# Schema_serre.net
KiCad netlist of a schematic drawn in EAGLE
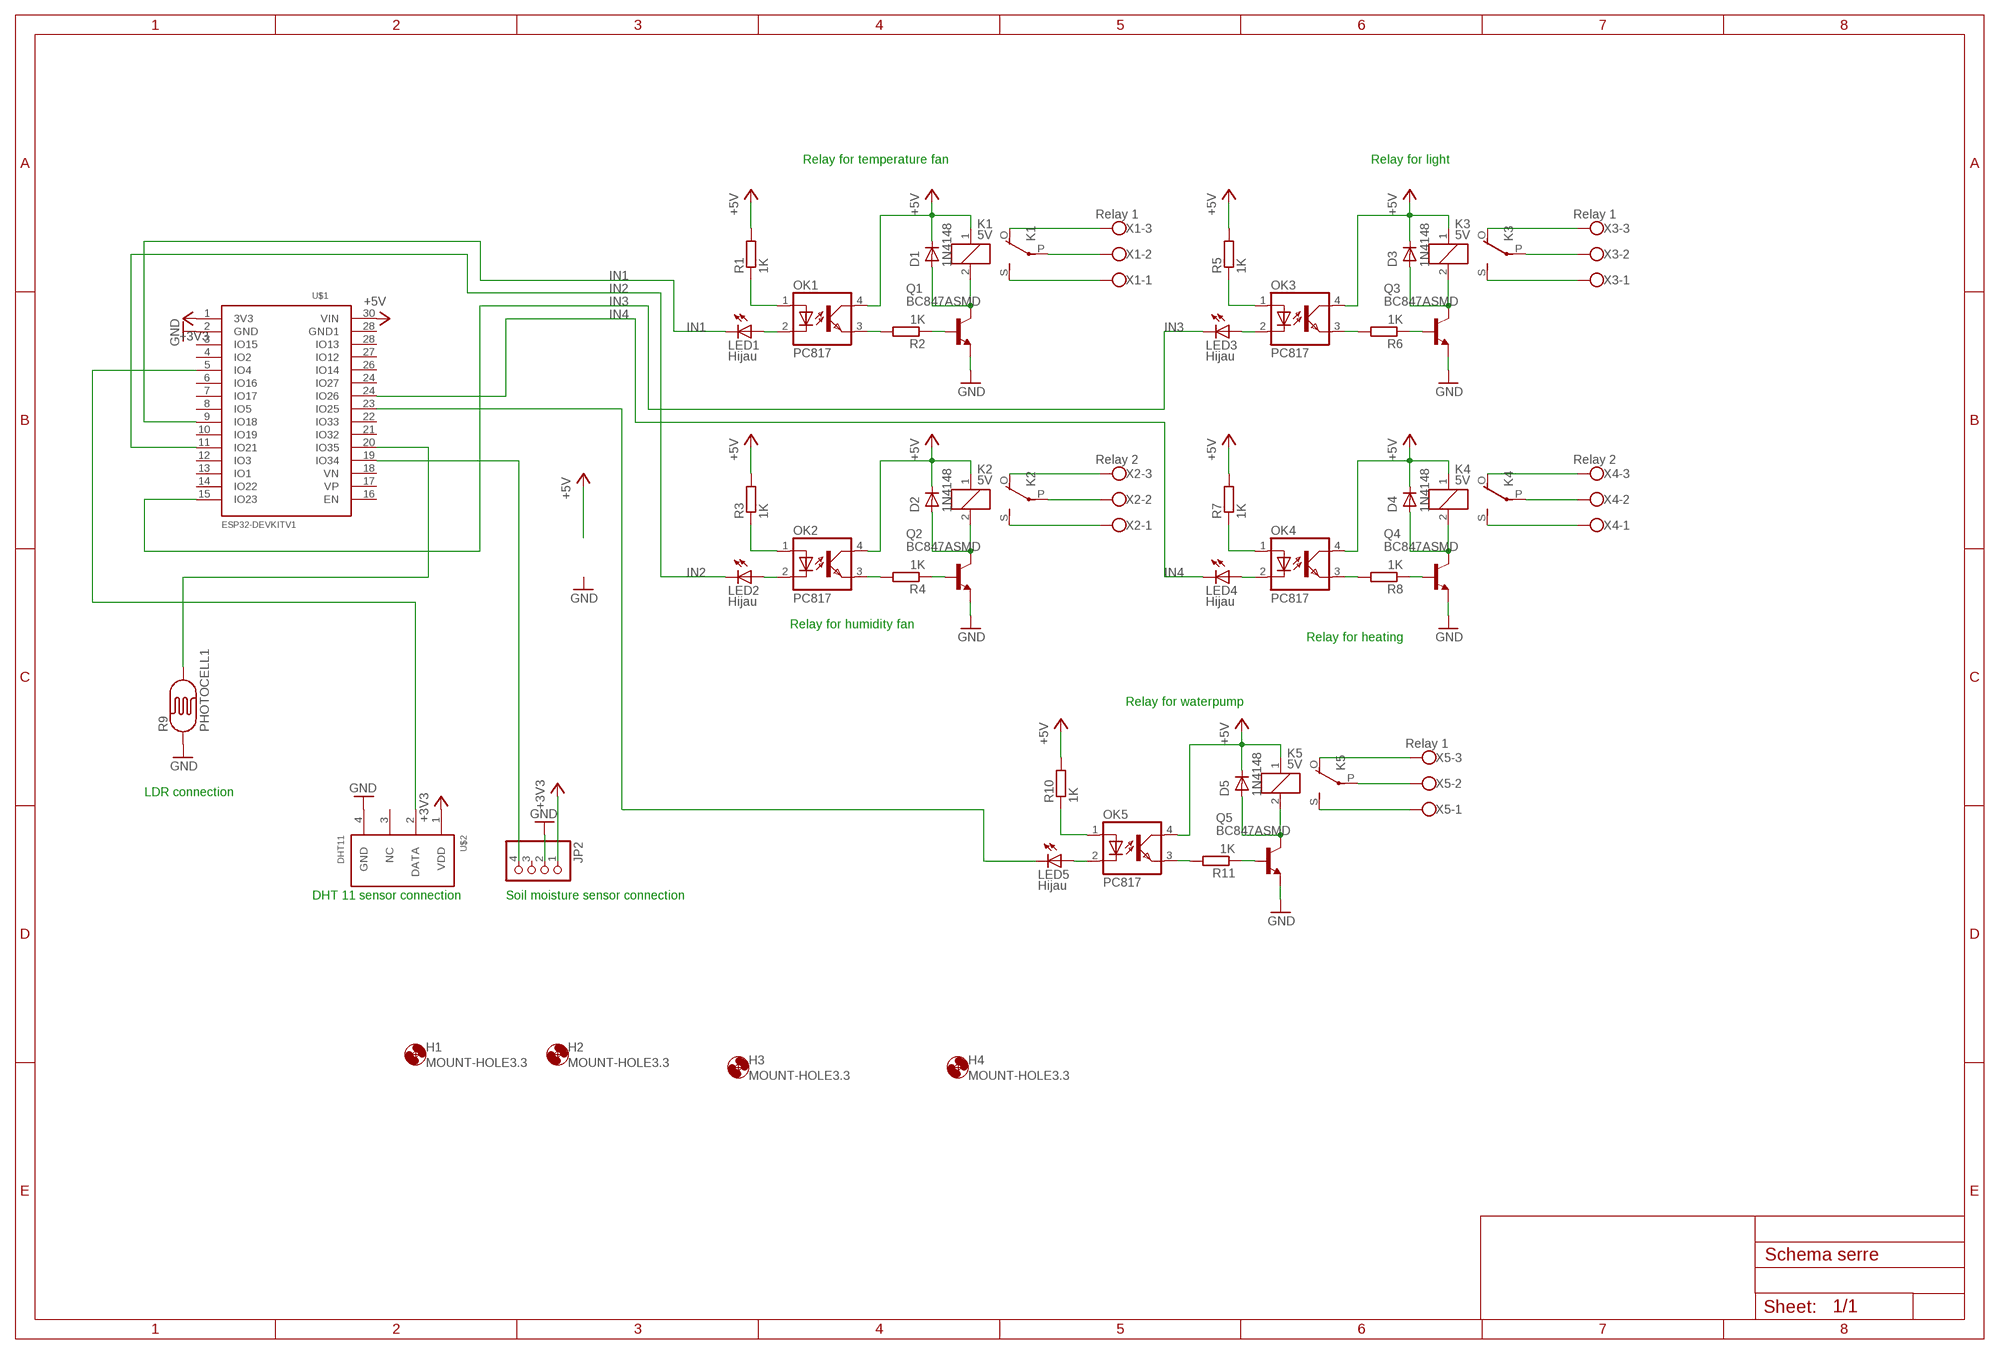
[diagram p0: schematic, sheet 1]

(export (version "E")
  (design (tool "Eeschema 10.0.6"))
  (components
    (comp (ref "D1")
      (value "1N4148")
      (footprint "eagle-import:SMA-DO214AC")
      (libsource (lib "eagle-import") (part "GF1"))
    )
    (comp (ref "D2")
      (value "1N4148")
      (footprint "eagle-import:SMA-DO214AC")
      (libsource (lib "eagle-import") (part "GF1"))
    )
    (comp (ref "D3")
      (value "1N4148")
      (footprint "eagle-import:SMA-DO214AC")
      (libsource (lib "eagle-import") (part "GF1"))
    )
    (comp (ref "D4")
      (value "1N4148")
      (footprint "eagle-import:SMA-DO214AC")
      (libsource (lib "eagle-import") (part "GF1"))
    )
    (comp (ref "D5")
      (value "1N4148")
      (footprint "eagle-import:SMA-DO214AC")
      (libsource (lib "eagle-import") (part "GF1"))
    )
    (comp (ref "H1")
      (value "MOUNT-HOLE3.3")
      (footprint "eagle-import:3,3")
      (libsource (lib "eagle-import") (part "MOUNT-HOLE3.3"))
    )
    (comp (ref "H2")
      (value "MOUNT-HOLE3.3")
      (footprint "eagle-import:3,3")
      (libsource (lib "eagle-import") (part "MOUNT-HOLE3.3"))
    )
    (comp (ref "H3")
      (value "MOUNT-HOLE3.3")
      (footprint "eagle-import:3,3")
      (libsource (lib "eagle-import") (part "MOUNT-HOLE3.3"))
    )
    (comp (ref "H4")
      (value "MOUNT-HOLE3.3")
      (footprint "eagle-import:3,3")
      (libsource (lib "eagle-import") (part "MOUNT-HOLE3.3"))
    )
    (comp (ref "JP2")
      (value "PINHD-1X4")
      (footprint "eagle-import:1X04")
      (libsource (lib "eagle-import") (part "PINHD-1X4"))
    )
    (comp (ref "K1")
      (value "5V")
      (footprint "eagle-import:ZF112")
      (libsource (lib "eagle-import") (part "ZF112"))
    )
    (comp (ref "K2")
      (value "5V")
      (footprint "eagle-import:ZF112")
      (libsource (lib "eagle-import") (part "ZF112"))
    )
    (comp (ref "K3")
      (value "5V")
      (footprint "eagle-import:ZF112")
      (libsource (lib "eagle-import") (part "ZF112"))
    )
    (comp (ref "K4")
      (value "5V")
      (footprint "eagle-import:ZF112")
      (libsource (lib "eagle-import") (part "ZF112"))
    )
    (comp (ref "K5")
      (value "5V")
      (footprint "eagle-import:ZF112")
      (libsource (lib "eagle-import") (part "ZF112"))
    )
    (comp (ref "LED1")
      (value "Hijau")
      (footprint "eagle-import:LED3MM")
      (libsource (lib "eagle-import") (part "LED3MM"))
    )
    (comp (ref "LED2")
      (value "Hijau")
      (footprint "eagle-import:LED3MM")
      (libsource (lib "eagle-import") (part "LED3MM"))
    )
    (comp (ref "LED3")
      (value "Hijau")
      (footprint "eagle-import:LED3MM")
      (libsource (lib "eagle-import") (part "LED3MM"))
    )
    (comp (ref "LED4")
      (value "Hijau")
      (footprint "eagle-import:LED3MM")
      (libsource (lib "eagle-import") (part "LED3MM"))
    )
    (comp (ref "LED5")
      (value "Hijau")
      (footprint "eagle-import:LED3MM")
      (libsource (lib "eagle-import") (part "LED3MM"))
    )
    (comp (ref "OK1")
      (value "PC817")
      (footprint "eagle-import:DIL04")
      (fields (field (name "MPN") "PC817X4J000F"))
      (libsource (lib "eagle-import") (part "PC817"))
    )
    (comp (ref "OK2")
      (value "PC817")
      (footprint "eagle-import:DIL04")
      (fields (field (name "MPN") "PC817X4J000F"))
      (libsource (lib "eagle-import") (part "PC817"))
    )
    (comp (ref "OK3")
      (value "PC817")
      (footprint "eagle-import:DIL04")
      (fields (field (name "MPN") "PC817X4J000F"))
      (libsource (lib "eagle-import") (part "PC817"))
    )
    (comp (ref "OK4")
      (value "PC817")
      (footprint "eagle-import:DIL04")
      (fields (field (name "MPN") "PC817X4J000F"))
      (libsource (lib "eagle-import") (part "PC817"))
    )
    (comp (ref "OK5")
      (value "PC817")
      (footprint "eagle-import:DIL04")
      (fields (field (name "MPN") "PC817X4J000F"))
      (libsource (lib "eagle-import") (part "PC817"))
    )
    (comp (ref "Q1")
      (value "BC847ASMD")
      (footprint "eagle-import:SOT23")
      (libsource (lib "eagle-import") (part "BC847SMDA"))
    )
    (comp (ref "Q2")
      (value "BC847ASMD")
      (footprint "eagle-import:SOT23")
      (libsource (lib "eagle-import") (part "BC847SMDA"))
    )
    (comp (ref "Q3")
      (value "BC847ASMD")
      (footprint "eagle-import:SOT23")
      (libsource (lib "eagle-import") (part "BC847SMDA"))
    )
    (comp (ref "Q4")
      (value "BC847ASMD")
      (footprint "eagle-import:SOT23")
      (libsource (lib "eagle-import") (part "BC847SMDA"))
    )
    (comp (ref "Q5")
      (value "BC847ASMD")
      (footprint "eagle-import:SOT23")
      (libsource (lib "eagle-import") (part "BC847SMDA"))
    )
    (comp (ref "R1")
      (value "1K")
      (footprint "eagle-import:R1206")
      (libsource (lib "eagle-import") (part "R-EU_R1206"))
    )
    (comp (ref "R2")
      (value "1K")
      (footprint "eagle-import:R1206")
      (libsource (lib "eagle-import") (part "R-EU_R1206"))
    )
    (comp (ref "R3")
      (value "1K")
      (footprint "eagle-import:R1206")
      (libsource (lib "eagle-import") (part "R-EU_R1206"))
    )
    (comp (ref "R4")
      (value "1K")
      (footprint "eagle-import:R1206")
      (libsource (lib "eagle-import") (part "R-EU_R1206"))
    )
    (comp (ref "R5")
      (value "1K")
      (footprint "eagle-import:R1206")
      (libsource (lib "eagle-import") (part "R-EU_R1206"))
    )
    (comp (ref "R6")
      (value "1K")
      (footprint "eagle-import:R1206")
      (libsource (lib "eagle-import") (part "R-EU_R1206"))
    )
    (comp (ref "R7")
      (value "1K")
      (footprint "eagle-import:R1206")
      (libsource (lib "eagle-import") (part "R-EU_R1206"))
    )
    (comp (ref "R8")
      (value "1K")
      (footprint "eagle-import:R1206")
      (libsource (lib "eagle-import") (part "R-EU_R1206"))
    )
    (comp (ref "R9")
      (value "PHOTOCELL1")
      (footprint "eagle-import:LDR_OFFBOARD")
      (libsource (lib "eagle-import") (part "PHOTOCELL1"))
    )
    (comp (ref "R10")
      (value "1K")
      (footprint "eagle-import:R1206")
      (libsource (lib "eagle-import") (part "R-EU_R1206"))
    )
    (comp (ref "R11")
      (value "1K")
      (footprint "eagle-import:R1206")
      (libsource (lib "eagle-import") (part "R-EU_R1206"))
    )
    (comp (ref "U$1")
      (value "ESP32DEVKITV1")
      (footprint "eagle-import:ESP32-DEVKITV1")
      (libsource (lib "eagle-import") (part "ESP32DEVKITV1"))
    )
    (comp (ref "U$2")
      (value "DHT11")
      (footprint "eagle-import:DHT11")
      (libsource (lib "eagle-import") (part "DHT11"))
    )
    (comp (ref "X1")
      (value "Relay 1")
      (footprint "eagle-import:W237-103")
      (fields (field (name "MPN") "237-103"))
      (libsource (lib "eagle-import") (part "W237-103"))
    )
    (comp (ref "X2")
      (value "Relay 2")
      (footprint "eagle-import:W237-103")
      (fields (field (name "MPN") "237-103"))
      (libsource (lib "eagle-import") (part "W237-103"))
    )
    (comp (ref "X3")
      (value "Relay 1")
      (footprint "eagle-import:W237-103")
      (fields (field (name "MPN") "237-103"))
      (libsource (lib "eagle-import") (part "W237-103"))
    )
    (comp (ref "X4")
      (value "Relay 2")
      (footprint "eagle-import:W237-103")
      (fields (field (name "MPN") "237-103"))
      (libsource (lib "eagle-import") (part "W237-103"))
    )
    (comp (ref "X5")
      (value "Relay 1")
      (footprint "eagle-import:W237-103")
      (fields (field (name "MPN") "237-103"))
      (libsource (lib "eagle-import") (part "W237-103"))
    )
  )
  (nets
    (net (code "1") (name "+3V3") (class "Default")
      (node (ref "JP2") (pin "1") (pinfunction "1_1") (pintype "passive"))
      (node (ref "U$1") (pin "1") (pinfunction "3V3_1") (pintype "bidirectional"))
      (node (ref "U$2") (pin "1") (pinfunction "VDD_1") (pintype "power_in"))
    )
    (net (code "2") (name "+5V") (class "Default")
      (node (ref "D1") (pin "K") (pinfunction "C_K") (pintype "passive"))
      (node (ref "D2") (pin "K") (pinfunction "C_K") (pintype "passive"))
      (node (ref "D3") (pin "K") (pinfunction "C_K") (pintype "passive"))
      (node (ref "D4") (pin "K") (pinfunction "C_K") (pintype "passive"))
      (node (ref "D5") (pin "K") (pinfunction "C_K") (pintype "passive"))
      (node (ref "K1") (pin "1") (pinfunction "1_1") (pintype "passive"))
      (node (ref "K2") (pin "1") (pinfunction "1_1") (pintype "passive"))
      (node (ref "K3") (pin "1") (pinfunction "1_1") (pintype "passive"))
      (node (ref "K4") (pin "1") (pinfunction "1_1") (pintype "passive"))
      (node (ref "K5") (pin "1") (pinfunction "1_1") (pintype "passive"))
      (node (ref "OK1") (pin "4") (pinfunction "COL_4") (pintype "passive"))
      (node (ref "OK2") (pin "4") (pinfunction "COL_4") (pintype "passive"))
      (node (ref "OK3") (pin "4") (pinfunction "COL_4") (pintype "passive"))
      (node (ref "OK4") (pin "4") (pinfunction "COL_4") (pintype "passive"))
      (node (ref "OK5") (pin "4") (pinfunction "COL_4") (pintype "passive"))
      (node (ref "R1") (pin "2") (pinfunction "2_2") (pintype "passive"))
      (node (ref "R10") (pin "2") (pinfunction "2_2") (pintype "passive"))
      (node (ref "R3") (pin "2") (pinfunction "2_2") (pintype "passive"))
      (node (ref "R5") (pin "2") (pinfunction "2_2") (pintype "passive"))
      (node (ref "R7") (pin "2") (pinfunction "2_2") (pintype "passive"))
      (node (ref "U$1") (pin "30") (pinfunction "VIN_30") (pintype "bidirectional"))
    )
    (net (code "3") (name "/IN1") (class "Default")
      (node (ref "LED1") (pin "K") (pinfunction "C_K") (pintype "passive"))
      (node (ref "LED5") (pin "K") (pinfunction "C_K") (pintype "passive"))
      (node (ref "U$1") (pin "23") (pinfunction "IO25_23") (pintype "bidirectional"))
      (node (ref "U$1") (pin "9") (pinfunction "IO18_9") (pintype "bidirectional"))
    )
    (net (code "4") (name "/IN2") (class "Default")
      (node (ref "LED2") (pin "K") (pinfunction "C_K") (pintype "passive"))
      (node (ref "U$1") (pin "11") (pinfunction "IO21_11") (pintype "bidirectional"))
    )
    (net (code "5") (name "/IN3") (class "Default")
      (node (ref "LED3") (pin "K") (pinfunction "C_K") (pintype "passive"))
      (node (ref "U$1") (pin "15") (pinfunction "IO23_15") (pintype "bidirectional"))
    )
    (net (code "6") (name "/IN4") (class "Default")
      (node (ref "LED4") (pin "K") (pinfunction "C_K") (pintype "passive"))
      (node (ref "U$1") (pin "24") (pinfunction "IO26_24") (pintype "bidirectional"))
    )
    (net (code "7") (name "GND") (class "Default")
      (node (ref "JP2") (pin "2") (pinfunction "2_2") (pintype "passive"))
      (node (ref "Q1") (pin "2") (pinfunction "E_2") (pintype "passive"))
      (node (ref "Q2") (pin "2") (pinfunction "E_2") (pintype "passive"))
      (node (ref "Q3") (pin "2") (pinfunction "E_2") (pintype "passive"))
      (node (ref "Q4") (pin "2") (pinfunction "E_2") (pintype "passive"))
      (node (ref "Q5") (pin "2") (pinfunction "E_2") (pintype "passive"))
      (node (ref "R9") (pin "1") (pinfunction "P$1_1") (pintype "bidirectional"))
      (node (ref "U$1") (pin "2") (pinfunction "GND_2") (pintype "bidirectional"))
      (node (ref "U$2") (pin "4") (pinfunction "GND_4") (pintype "power_in"))
    )
    (net (code "8") (name "Net-(OK1-A)") (class "Default")
      (node (ref "OK1") (pin "1") (pinfunction "A_1") (pintype "passive"))
      (node (ref "R1") (pin "1") (pinfunction "1_1") (pintype "passive"))
    )
    (net (code "9") (name "Net-(OK1-C)") (class "Default")
      (node (ref "LED1") (pin "A") (pinfunction "A_A") (pintype "passive"))
      (node (ref "OK1") (pin "2") (pinfunction "C_2") (pintype "passive"))
    )
    (net (code "10") (name "Net-(OK1-EMIT)") (class "Default")
      (node (ref "OK1") (pin "3") (pinfunction "EMIT_3") (pintype "passive"))
      (node (ref "R2") (pin "2") (pinfunction "2_2") (pintype "passive"))
    )
    (net (code "11") (name "Net-(OK2-A)") (class "Default")
      (node (ref "OK2") (pin "1") (pinfunction "A_1") (pintype "passive"))
      (node (ref "R3") (pin "1") (pinfunction "1_1") (pintype "passive"))
    )
    (net (code "12") (name "Net-(OK2-C)") (class "Default")
      (node (ref "LED2") (pin "A") (pinfunction "A_A") (pintype "passive"))
      (node (ref "OK2") (pin "2") (pinfunction "C_2") (pintype "passive"))
    )
    (net (code "13") (name "Net-(OK2-EMIT)") (class "Default")
      (node (ref "OK2") (pin "3") (pinfunction "EMIT_3") (pintype "passive"))
      (node (ref "R4") (pin "2") (pinfunction "2_2") (pintype "passive"))
    )
    (net (code "14") (name "Net-(OK3-A)") (class "Default")
      (node (ref "OK3") (pin "1") (pinfunction "A_1") (pintype "passive"))
      (node (ref "R5") (pin "1") (pinfunction "1_1") (pintype "passive"))
    )
    (net (code "15") (name "Net-(OK3-C)") (class "Default")
      (node (ref "LED3") (pin "A") (pinfunction "A_A") (pintype "passive"))
      (node (ref "OK3") (pin "2") (pinfunction "C_2") (pintype "passive"))
    )
    (net (code "16") (name "Net-(OK3-EMIT)") (class "Default")
      (node (ref "OK3") (pin "3") (pinfunction "EMIT_3") (pintype "passive"))
      (node (ref "R6") (pin "2") (pinfunction "2_2") (pintype "passive"))
    )
    (net (code "17") (name "Net-(OK4-A)") (class "Default")
      (node (ref "OK4") (pin "1") (pinfunction "A_1") (pintype "passive"))
      (node (ref "R7") (pin "1") (pinfunction "1_1") (pintype "passive"))
    )
    (net (code "18") (name "Net-(OK4-C)") (class "Default")
      (node (ref "LED4") (pin "A") (pinfunction "A_A") (pintype "passive"))
      (node (ref "OK4") (pin "2") (pinfunction "C_2") (pintype "passive"))
    )
    (net (code "19") (name "Net-(OK4-EMIT)") (class "Default")
      (node (ref "OK4") (pin "3") (pinfunction "EMIT_3") (pintype "passive"))
      (node (ref "R8") (pin "2") (pinfunction "2_2") (pintype "passive"))
    )
    (net (code "20") (name "Net-(OK5-A)") (class "Default")
      (node (ref "OK5") (pin "1") (pinfunction "A_1") (pintype "passive"))
      (node (ref "R10") (pin "1") (pinfunction "1_1") (pintype "passive"))
    )
    (net (code "21") (name "Net-(OK5-C)") (class "Default")
      (node (ref "LED5") (pin "A") (pinfunction "A_A") (pintype "passive"))
      (node (ref "OK5") (pin "2") (pinfunction "C_2") (pintype "passive"))
    )
    (net (code "22") (name "Net-(OK5-EMIT)") (class "Default")
      (node (ref "OK5") (pin "3") (pinfunction "EMIT_3") (pintype "passive"))
      (node (ref "R11") (pin "2") (pinfunction "2_2") (pintype "passive"))
    )
    (net (code "23") (name "Net-(Q1-B)") (class "Default")
      (node (ref "Q1") (pin "1") (pinfunction "B_1") (pintype "passive"))
      (node (ref "R2") (pin "1") (pinfunction "1_1") (pintype "passive"))
    )
    (net (code "24") (name "Net-(Q1-C)") (class "Default")
      (node (ref "D1") (pin "A") (pinfunction "A_A") (pintype "passive"))
      (node (ref "K1") (pin "2") (pinfunction "2_2") (pintype "passive"))
      (node (ref "Q1") (pin "3") (pinfunction "C_3") (pintype "passive"))
    )
    (net (code "25") (name "Net-(Q2-B)") (class "Default")
      (node (ref "Q2") (pin "1") (pinfunction "B_1") (pintype "passive"))
      (node (ref "R4") (pin "1") (pinfunction "1_1") (pintype "passive"))
    )
    (net (code "26") (name "Net-(Q2-C)") (class "Default")
      (node (ref "D2") (pin "A") (pinfunction "A_A") (pintype "passive"))
      (node (ref "K2") (pin "2") (pinfunction "2_2") (pintype "passive"))
      (node (ref "Q2") (pin "3") (pinfunction "C_3") (pintype "passive"))
    )
    (net (code "27") (name "Net-(Q3-B)") (class "Default")
      (node (ref "Q3") (pin "1") (pinfunction "B_1") (pintype "passive"))
      (node (ref "R6") (pin "1") (pinfunction "1_1") (pintype "passive"))
    )
    (net (code "28") (name "Net-(Q3-C)") (class "Default")
      (node (ref "D3") (pin "A") (pinfunction "A_A") (pintype "passive"))
      (node (ref "K3") (pin "2") (pinfunction "2_2") (pintype "passive"))
      (node (ref "Q3") (pin "3") (pinfunction "C_3") (pintype "passive"))
    )
    (net (code "29") (name "Net-(Q4-B)") (class "Default")
      (node (ref "Q4") (pin "1") (pinfunction "B_1") (pintype "passive"))
      (node (ref "R8") (pin "1") (pinfunction "1_1") (pintype "passive"))
    )
    (net (code "30") (name "Net-(Q4-C)") (class "Default")
      (node (ref "D4") (pin "A") (pinfunction "A_A") (pintype "passive"))
      (node (ref "K4") (pin "2") (pinfunction "2_2") (pintype "passive"))
      (node (ref "Q4") (pin "3") (pinfunction "C_3") (pintype "passive"))
    )
    (net (code "31") (name "Net-(Q5-B)") (class "Default")
      (node (ref "Q5") (pin "1") (pinfunction "B_1") (pintype "passive"))
      (node (ref "R11") (pin "1") (pinfunction "1_1") (pintype "passive"))
    )
    (net (code "32") (name "Net-(Q5-C)") (class "Default")
      (node (ref "D5") (pin "A") (pinfunction "A_A") (pintype "passive"))
      (node (ref "K5") (pin "2") (pinfunction "2_2") (pintype "passive"))
      (node (ref "Q5") (pin "3") (pinfunction "C_3") (pintype "passive"))
    )
    (net (code "33") (name "Net-(R9-P$2)") (class "Default")
      (node (ref "R9") (pin "2") (pinfunction "P$2_2") (pintype "bidirectional"))
      (node (ref "U$1") (pin "20") (pinfunction "IO35_20") (pintype "bidirectional"))
    )
    (net (code "34") (name "Net-(U$1-IO4)") (class "Default")
      (node (ref "U$1") (pin "5") (pinfunction "IO4_5") (pintype "bidirectional"))
      (node (ref "U$2") (pin "2") (pinfunction "DATA_2") (pintype "bidirectional"))
    )
    (net (code "35") (name "Net-(U$1-IO34)") (class "Default")
      (node (ref "JP2") (pin "4") (pinfunction "4_4") (pintype "passive"))
      (node (ref "U$1") (pin "19") (pinfunction "IO34_19") (pintype "bidirectional"))
    )
    (net (code "36") (name "Net-(X1A-KL)") (class "Default")
      (node (ref "K1") (pin "S") (pinfunction "S_S") (pintype "passive"))
      (node (ref "X1") (pin "1") (pinfunction "KL_1") (pintype "passive"))
    )
    (net (code "37") (name "Net-(X1B-KL)") (class "Default")
      (node (ref "K1") (pin "P") (pinfunction "P_P") (pintype "passive"))
      (node (ref "X1") (pin "2") (pinfunction "KL_2") (pintype "passive"))
    )
    (net (code "38") (name "Net-(X1C-KL)") (class "Default")
      (node (ref "K1") (pin "O") (pinfunction "O_O") (pintype "passive"))
      (node (ref "X1") (pin "3") (pinfunction "KL_3") (pintype "passive"))
    )
    (net (code "39") (name "Net-(X2A-KL)") (class "Default")
      (node (ref "K2") (pin "S") (pinfunction "S_S") (pintype "passive"))
      (node (ref "X2") (pin "1") (pinfunction "KL_1") (pintype "passive"))
    )
    (net (code "40") (name "Net-(X2B-KL)") (class "Default")
      (node (ref "K2") (pin "P") (pinfunction "P_P") (pintype "passive"))
      (node (ref "X2") (pin "2") (pinfunction "KL_2") (pintype "passive"))
    )
    (net (code "41") (name "Net-(X2C-KL)") (class "Default")
      (node (ref "K2") (pin "O") (pinfunction "O_O") (pintype "passive"))
      (node (ref "X2") (pin "3") (pinfunction "KL_3") (pintype "passive"))
    )
    (net (code "42") (name "Net-(X3A-KL)") (class "Default")
      (node (ref "K3") (pin "S") (pinfunction "S_S") (pintype "passive"))
      (node (ref "X3") (pin "1") (pinfunction "KL_1") (pintype "passive"))
    )
    (net (code "43") (name "Net-(X3B-KL)") (class "Default")
      (node (ref "K3") (pin "P") (pinfunction "P_P") (pintype "passive"))
      (node (ref "X3") (pin "2") (pinfunction "KL_2") (pintype "passive"))
    )
    (net (code "44") (name "Net-(X3C-KL)") (class "Default")
      (node (ref "K3") (pin "O") (pinfunction "O_O") (pintype "passive"))
      (node (ref "X3") (pin "3") (pinfunction "KL_3") (pintype "passive"))
    )
    (net (code "45") (name "Net-(X4A-KL)") (class "Default")
      (node (ref "K4") (pin "S") (pinfunction "S_S") (pintype "passive"))
      (node (ref "X4") (pin "1") (pinfunction "KL_1") (pintype "passive"))
    )
    (net (code "46") (name "Net-(X4B-KL)") (class "Default")
      (node (ref "K4") (pin "P") (pinfunction "P_P") (pintype "passive"))
      (node (ref "X4") (pin "2") (pinfunction "KL_2") (pintype "passive"))
    )
    (net (code "47") (name "Net-(X4C-KL)") (class "Default")
      (node (ref "K4") (pin "O") (pinfunction "O_O") (pintype "passive"))
      (node (ref "X4") (pin "3") (pinfunction "KL_3") (pintype "passive"))
    )
    (net (code "48") (name "Net-(X5A-KL)") (class "Default")
      (node (ref "K5") (pin "S") (pinfunction "S_S") (pintype "passive"))
      (node (ref "X5") (pin "1") (pinfunction "KL_1") (pintype "passive"))
    )
    (net (code "49") (name "Net-(X5B-KL)") (class "Default")
      (node (ref "K5") (pin "P") (pinfunction "P_P") (pintype "passive"))
      (node (ref "X5") (pin "2") (pinfunction "KL_2") (pintype "passive"))
    )
    (net (code "50") (name "Net-(X5C-KL)") (class "Default")
      (node (ref "K5") (pin "O") (pinfunction "O_O") (pintype "passive"))
      (node (ref "X5") (pin "3") (pinfunction "KL_3") (pintype "passive"))
    )
    (net (code "51") (name "unconnected-(JP2-Pad3)") (class "Default")
      (node (ref "JP2") (pin "3") (pinfunction "3_3") (pintype "passive"))
    )
    (net (code "52") (name "unconnected-(U$1-EN-Pad16)") (class "Default")
      (node (ref "U$1") (pin "16") (pinfunction "EN_16") (pintype "bidirectional"))
    )
    (net (code "53") (name "unconnected-(U$1-GND1-Pad28)") (class "Default")
      (node (ref "U$1") (pin "28") (pinfunction "GND1_28") (pintype "bidirectional"))
    )
    (net (code "54") (name "unconnected-(U$1-IO1-Pad13)") (class "Default")
      (node (ref "U$1") (pin "13") (pinfunction "IO1_13") (pintype "bidirectional"))
    )
    (net (code "55") (name "unconnected-(U$1-IO2-Pad4)") (class "Default")
      (node (ref "U$1") (pin "4") (pinfunction "IO2_4") (pintype "bidirectional"))
    )
    (net (code "56") (name "unconnected-(U$1-IO3-Pad12)") (class "Default")
      (node (ref "U$1") (pin "12") (pinfunction "IO3_12") (pintype "bidirectional"))
    )
    (net (code "57") (name "unconnected-(U$1-IO5-Pad8)") (class "Default")
      (node (ref "U$1") (pin "8") (pinfunction "IO5_8") (pintype "bidirectional"))
    )
    (net (code "58") (name "unconnected-(U$1-IO12-Pad27)") (class "Default")
      (node (ref "U$1") (pin "27") (pinfunction "IO12_27") (pintype "bidirectional"))
    )
    (net (code "59") (name "unconnected-(U$1-IO13-Pad28)") (class "Default")
      (node (ref "U$1") (pin "28") (pinfunction "IO13_28") (pintype "bidirectional"))
    )
    (net (code "60") (name "unconnected-(U$1-IO14-Pad26)") (class "Default")
      (node (ref "U$1") (pin "26") (pinfunction "IO14_26") (pintype "bidirectional"))
    )
    (net (code "61") (name "unconnected-(U$1-IO15-Pad3)") (class "Default")
      (node (ref "U$1") (pin "3") (pinfunction "IO15_3") (pintype "bidirectional"))
    )
    (net (code "62") (name "unconnected-(U$1-IO16-Pad6)") (class "Default")
      (node (ref "U$1") (pin "6") (pinfunction "IO16_6") (pintype "bidirectional"))
    )
    (net (code "63") (name "unconnected-(U$1-IO17-Pad7)") (class "Default")
      (node (ref "U$1") (pin "7") (pinfunction "IO17_7") (pintype "bidirectional"))
    )
    (net (code "64") (name "unconnected-(U$1-IO19-Pad10)") (class "Default")
      (node (ref "U$1") (pin "10") (pinfunction "IO19_10") (pintype "bidirectional"))
    )
    (net (code "65") (name "unconnected-(U$1-IO22-Pad14)") (class "Default")
      (node (ref "U$1") (pin "14") (pinfunction "IO22_14") (pintype "bidirectional"))
    )
    (net (code "66") (name "unconnected-(U$1-IO27-Pad24)") (class "Default")
      (node (ref "U$1") (pin "24") (pinfunction "IO27_24") (pintype "bidirectional"))
    )
    (net (code "67") (name "unconnected-(U$1-IO32-Pad21)") (class "Default")
      (node (ref "U$1") (pin "21") (pinfunction "IO32_21") (pintype "bidirectional"))
    )
    (net (code "68") (name "unconnected-(U$1-IO33-Pad22)") (class "Default")
      (node (ref "U$1") (pin "22") (pinfunction "IO33_22") (pintype "bidirectional"))
    )
    (net (code "69") (name "unconnected-(U$1-VN-Pad18)") (class "Default")
      (node (ref "U$1") (pin "18") (pinfunction "VN_18") (pintype "bidirectional"))
    )
    (net (code "70") (name "unconnected-(U$1-VP-Pad17)") (class "Default")
      (node (ref "U$1") (pin "17") (pinfunction "VP_17") (pintype "bidirectional"))
    )
    (net (code "71") (name "unconnected-(U$2-NC-Pad3)") (class "Default")
      (node (ref "U$2") (pin "3") (pinfunction "NC_3") (pintype "bidirectional"))
    )
  )
)
